# CLK_Protection.net
KiCad netlist of a schematic drawn in Altium Designer
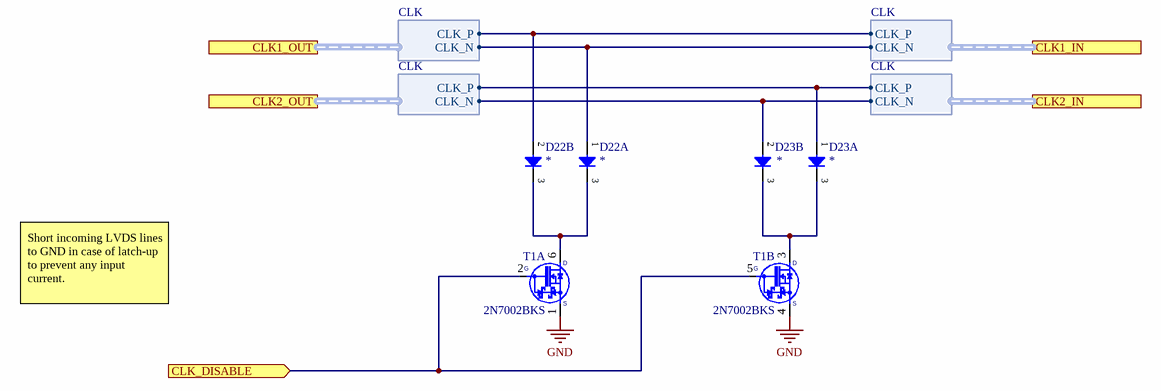
[diagram p0: CLK_Protection.SchDoc]

(export (version "E")
  (design (tool "Eeschema 10.0.6"))
  (components
    (comp (ref "D22")
      (value "*")
      (footprint "ICs And Semiconductors SMD:SOT65P210X110-3N")
      (fields (field (name "MANUFACTURER PART NUMBER") "BAT1705WH6327"))
      (libsource (lib "ICs_And_Semiconductors") (part "BAT1705WH"))
    )
    (comp (ref "D23")
      (value "*")
      (footprint "ICs And Semiconductors SMD:SOT65P210X110-3N")
      (fields (field (name "MANUFACTURER PART NUMBER") "BAT1705WH6327"))
      (libsource (lib "ICs_And_Semiconductors") (part "BAT1705WH"))
    )
    (comp (ref "T1")
      (value "2N7002BKS")
      (footprint "SOT65P210X110-6N")
      (description "60V, 300mA Dual N-Channel Trench MOSFET")
      (fields
        (field (name "MANUFACTURER") "NXP SEMICONDUCTORS")
        (field (name "MANUFACTURER PART NUMBER") "2N7002BKS6")
        (field (name "AUTHOR") "CERN DEM JLC")
      )
      (libsource (lib "ICs And Semiconductors") (part "2N7002BKS"))
    )
  )
  (nets
    (net (code "2") (name "/CLK_DISABLE") (class "Default")
      (node (ref "T1") (pin "2") (pinfunction "G_2") (pintype "passive"))
      (node (ref "T1") (pin "5") (pinfunction "G_5") (pintype "passive"))
    )
    (net (code "4") (name "GND") (class "Default")
      (node (ref "T1") (pin "1") (pinfunction "S_1") (pintype "passive"))
      (node (ref "T1") (pin "4") (pinfunction "S_4") (pintype "passive"))
    )
    (net (code "5") (name "Net-(D22A-COMC)") (class "Default")
      (node (ref "D22") (pin "3") (pinfunction "COMC_3") (pintype "passive"))
      (node (ref "T1") (pin "6") (pinfunction "D_6") (pintype "passive"))
    )
    (net (code "6") (name "Net-(D23A-COMC)") (class "Default")
      (node (ref "D23") (pin "3") (pinfunction "COMC_3") (pintype "passive"))
      (node (ref "T1") (pin "3") (pinfunction "D_3") (pintype "passive"))
    )
    (net (code "7") (name "unconnected-(D22A-A-Pad1)") (class "Default")
      (node (ref "D22") (pin "1") (pinfunction "A_1") (pintype "passive"))
    )
    (net (code "8") (name "unconnected-(D22B-A-Pad2)") (class "Default")
      (node (ref "D22") (pin "2") (pinfunction "A_2") (pintype "passive"))
    )
    (net (code "9") (name "unconnected-(D23A-A-Pad1)") (class "Default")
      (node (ref "D23") (pin "1") (pinfunction "A_1") (pintype "passive"))
    )
    (net (code "10") (name "unconnected-(D23B-A-Pad2)") (class "Default")
      (node (ref "D23") (pin "2") (pinfunction "A_2") (pintype "passive"))
    )
  )
)
